# arduino_Uno_mod_bt.net
KiCad netlist of a schematic drawn in EAGLE
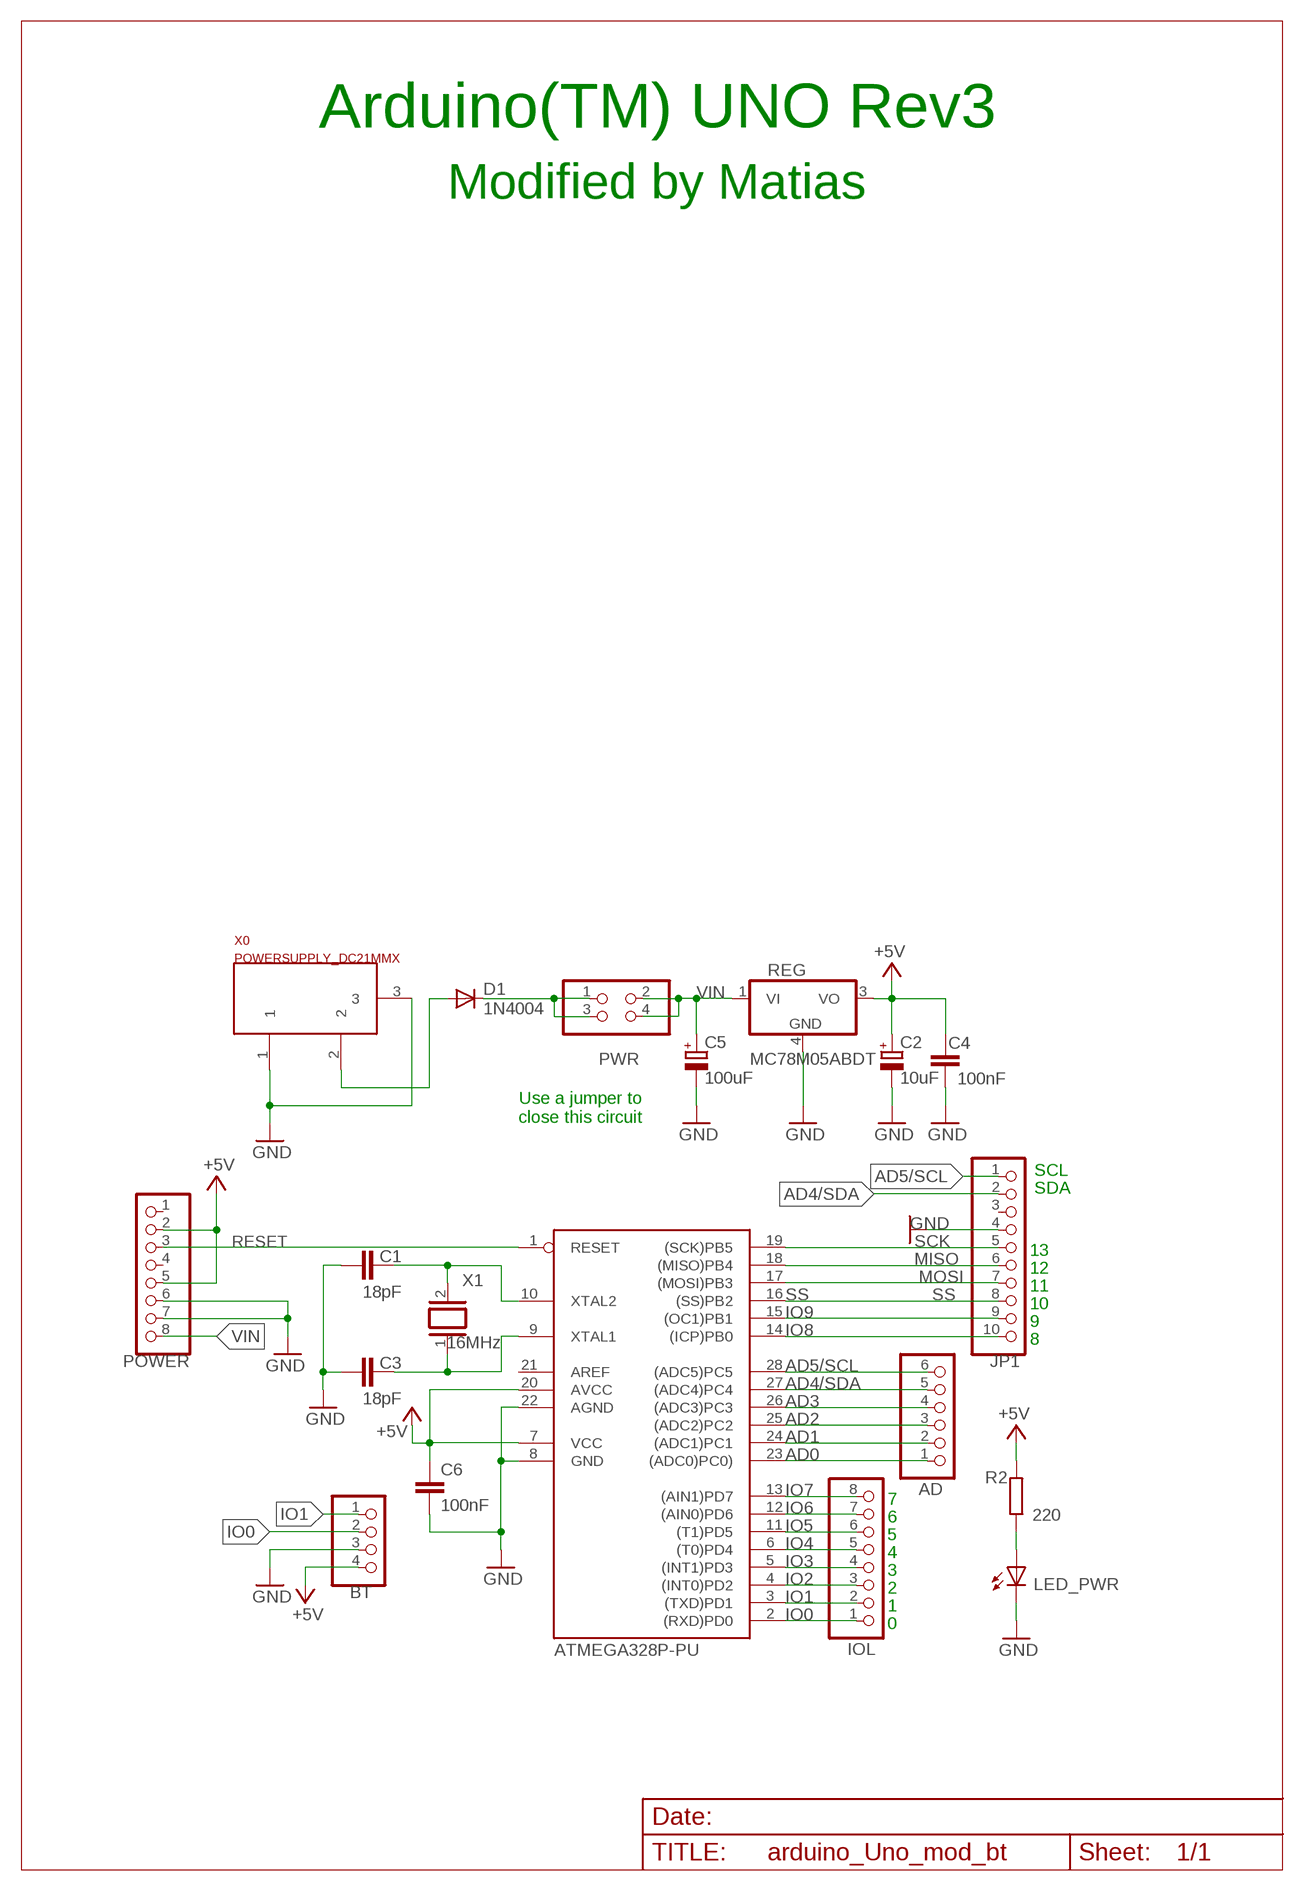
[diagram p0: schematic, sheet 1]

(export (version "E")
  (design (tool "Eeschema 10.0.6"))
  (components
    (comp (ref "AD")
      (value "6x1F-H8.5")
      (footprint "eagle-import:1X06")
      (libsource (lib "eagle-import") (part "PINHD-1X6"))
    )
    (comp (ref "BT")
      (value "PINHD-1X4/90")
      (footprint "eagle-import:1X04_90")
      (libsource (lib "eagle-import") (part "PINHD-1X4/90"))
    )
    (comp (ref "C1")
      (value "18pF")
      (footprint "eagle-import:C025-025X050")
      (libsource (lib "eagle-import") (part "C-EU025-025X050"))
    )
    (comp (ref "C2")
      (value "10uF")
      (footprint "eagle-import:E2,5-5")
      (libsource (lib "eagle-import") (part "CPOL-EUE2.5-5"))
    )
    (comp (ref "C3")
      (value "18pF")
      (footprint "eagle-import:C025-025X050")
      (libsource (lib "eagle-import") (part "C-EU025-025X050"))
    )
    (comp (ref "C4")
      (value "100nF")
      (footprint "eagle-import:C025-025X050")
      (libsource (lib "eagle-import") (part "C-EU025-025X050"))
    )
    (comp (ref "C5")
      (value "100uF")
      (footprint "eagle-import:E2-5")
      (libsource (lib "eagle-import") (part "rcl_334_CPOL-EUE2-5"))
    )
    (comp (ref "C6")
      (value "100nF")
      (footprint "eagle-import:C025-025X050")
      (libsource (lib "eagle-import") (part "C-EU025-025X050"))
    )
    (comp (ref "D1")
      (value "1N4004")
      (footprint "eagle-import:DO41-10")
      (libsource (lib "eagle-import") (part "1N4004"))
    )
    (comp (ref "IOL")
      (value "8x1F-H8.5")
      (footprint "eagle-import:1X08")
      (libsource (lib "eagle-import") (part "PINHD-1X8"))
    )
    (comp (ref "JP1")
      (value "PINHD-1X10")
      (footprint "eagle-import:1X10")
      (libsource (lib "eagle-import") (part "PINHD-1X10"))
    )
    (comp (ref "LED_PWR")
      (value "LED3MM")
      (footprint "eagle-import:LED3MM")
      (libsource (lib "eagle-import") (part "LED3MM"))
    )
    (comp (ref "POWER")
      (value "8x1F-H8.5")
      (footprint "eagle-import:1X08")
      (libsource (lib "eagle-import") (part "PINHD-1X8"))
    )
    (comp (ref "PWR")
      (value "PINHD-2X2")
      (footprint "eagle-import:2X02")
      (libsource (lib "eagle-import") (part "PINHD-2X2"))
    )
    (comp (ref "R2")
      (value "220")
      (footprint "eagle-import:R1206")
      (libsource (lib "eagle-import") (part "R-EU_R1206"))
    )
    (comp (ref "REG")
      (value "MC78M05ABDT")
      (footprint "eagle-import:DPACK_3")
      (libsource (lib "eagle-import") (part "MC78M05ABDT"))
    )
    (comp (ref "X0")
      (value "POWERSUPPLY_DC21MMX")
      (footprint "eagle-import:POWERSUPPLY_DC-21MM")
      (libsource (lib "eagle-import") (part "POWERSUPPLY_DC21MMX"))
    )
    (comp (ref "X1")
      (value "16MHz")
      (footprint "eagle-import:QS")
      (libsource (lib "eagle-import") (part "XTAL/S"))
    )
    (comp (ref "ZU4")
      (value "ATMEGA328P-PU")
      (footprint "eagle-import:DIL28-3")
      (libsource (lib "eagle-import") (part "ATMEGA328P-PU"))
    )
  )
  (nets
    (net (code "1") (name "+5V") (class "Default")
      (node (ref "BT") (pin "4") (pinfunction "4_4") (pintype "passive"))
      (node (ref "C2") (pin "+") (pinfunction "+_+") (pintype "passive"))
      (node (ref "C4") (pin "2") (pinfunction "2_2") (pintype "passive"))
      (node (ref "C6") (pin "1") (pinfunction "1_1") (pintype "passive"))
      (node (ref "POWER") (pin "2") (pinfunction "2_2") (pintype "passive"))
      (node (ref "POWER") (pin "5") (pinfunction "5_5") (pintype "passive"))
      (node (ref "R2") (pin "2") (pinfunction "2_2") (pintype "passive"))
      (node (ref "REG") (pin "3") (pinfunction "VO_3") (pintype "passive"))
      (node (ref "ZU4") (pin "20") (pinfunction "AVCC_20") (pintype "power_in"))
      (node (ref "ZU4") (pin "7") (pinfunction "VCC_7") (pintype "power_in"))
    )
    (net (code "2") (name "/AD0") (class "Default")
      (node (ref "AD") (pin "1") (pinfunction "1_1") (pintype "passive"))
      (node (ref "ZU4") (pin "23") (pinfunction "(ADC0)PC0)_23") (pintype "bidirectional"))
    )
    (net (code "3") (name "/AD1") (class "Default")
      (node (ref "AD") (pin "2") (pinfunction "2_2") (pintype "passive"))
      (node (ref "ZU4") (pin "24") (pinfunction "(ADC1)PC1_24") (pintype "bidirectional"))
    )
    (net (code "4") (name "/AD2") (class "Default")
      (node (ref "AD") (pin "3") (pinfunction "3_3") (pintype "passive"))
      (node (ref "ZU4") (pin "25") (pinfunction "(ADC2)PC2_25") (pintype "bidirectional"))
    )
    (net (code "5") (name "/AD3") (class "Default")
      (node (ref "AD") (pin "4") (pinfunction "4_4") (pintype "passive"))
      (node (ref "ZU4") (pin "26") (pinfunction "(ADC3)PC3_26") (pintype "bidirectional"))
    )
    (net (code "6") (name "/IO2") (class "Default")
      (node (ref "IOL") (pin "3") (pinfunction "3_3") (pintype "passive"))
      (node (ref "ZU4") (pin "4") (pinfunction "(INT0)PD2_4") (pintype "bidirectional"))
    )
    (net (code "7") (name "/IO3") (class "Default")
      (node (ref "IOL") (pin "4") (pinfunction "4_4") (pintype "passive"))
      (node (ref "ZU4") (pin "5") (pinfunction "(INT1)PD3_5") (pintype "bidirectional"))
    )
    (net (code "8") (name "/IO4") (class "Default")
      (node (ref "IOL") (pin "5") (pinfunction "5_5") (pintype "passive"))
      (node (ref "ZU4") (pin "6") (pinfunction "(T0)PD4_6") (pintype "bidirectional"))
    )
    (net (code "9") (name "/IO5") (class "Default")
      (node (ref "IOL") (pin "6") (pinfunction "6_6") (pintype "passive"))
      (node (ref "ZU4") (pin "11") (pinfunction "(T1)PD5_11") (pintype "bidirectional"))
    )
    (net (code "10") (name "/IO6") (class "Default")
      (node (ref "IOL") (pin "7") (pinfunction "7_7") (pintype "passive"))
      (node (ref "ZU4") (pin "12") (pinfunction "(AIN0)PD6_12") (pintype "bidirectional"))
    )
    (net (code "11") (name "/IO7") (class "Default")
      (node (ref "IOL") (pin "8") (pinfunction "8_8") (pintype "passive"))
      (node (ref "ZU4") (pin "13") (pinfunction "(AIN1)PD7_13") (pintype "bidirectional"))
    )
    (net (code "12") (name "/IO8") (class "Default")
      (node (ref "JP1") (pin "10") (pinfunction "10_10") (pintype "passive"))
      (node (ref "ZU4") (pin "14") (pinfunction "(ICP)PB0_14") (pintype "bidirectional"))
    )
    (net (code "13") (name "/IO9") (class "Default")
      (node (ref "JP1") (pin "9") (pinfunction "9_9") (pintype "passive"))
      (node (ref "ZU4") (pin "15") (pinfunction "(OC1)PB1_15") (pintype "bidirectional"))
    )
    (net (code "14") (name "/MISO") (class "Default")
      (node (ref "JP1") (pin "6") (pinfunction "6_6") (pintype "passive"))
      (node (ref "ZU4") (pin "18") (pinfunction "(MISO)PB4_18") (pintype "bidirectional"))
    )
    (net (code "15") (name "/MOSI") (class "Default")
      (node (ref "JP1") (pin "7") (pinfunction "7_7") (pintype "passive"))
      (node (ref "ZU4") (pin "17") (pinfunction "(MOSI)PB3_17") (pintype "bidirectional"))
    )
    (net (code "16") (name "/RESET") (class "Default")
      (node (ref "POWER") (pin "3") (pinfunction "3_3") (pintype "passive"))
      (node (ref "ZU4") (pin "1") (pinfunction "RESET_1") (pintype "input"))
    )
    (net (code "17") (name "/SCK") (class "Default")
      (node (ref "JP1") (pin "5") (pinfunction "5_5") (pintype "passive"))
      (node (ref "ZU4") (pin "19") (pinfunction "(SCK)PB5_19") (pintype "bidirectional"))
    )
    (net (code "18") (name "/SS") (class "Default")
      (node (ref "JP1") (pin "8") (pinfunction "8_8") (pintype "passive"))
      (node (ref "ZU4") (pin "16") (pinfunction "(SS)PB2_16") (pintype "bidirectional"))
    )
    (net (code "19") (name "AD4{slash}SDA") (class "Default")
      (node (ref "AD") (pin "5") (pinfunction "5_5") (pintype "passive"))
      (node (ref "JP1") (pin "2") (pinfunction "2_2") (pintype "passive"))
      (node (ref "ZU4") (pin "27") (pinfunction "(ADC4)PC4_27") (pintype "bidirectional"))
    )
    (net (code "20") (name "AD5{slash}SCL") (class "Default")
      (node (ref "AD") (pin "6") (pinfunction "6_6") (pintype "passive"))
      (node (ref "JP1") (pin "1") (pinfunction "1_1") (pintype "passive"))
      (node (ref "ZU4") (pin "28") (pinfunction "(ADC5)PC5_28") (pintype "bidirectional"))
    )
    (net (code "21") (name "GND") (class "Default")
      (node (ref "BT") (pin "3") (pinfunction "3_3") (pintype "passive"))
      (node (ref "C1") (pin "1") (pinfunction "1_1") (pintype "passive"))
      (node (ref "C2") (pin "-") (pinfunction "-_-") (pintype "passive"))
      (node (ref "C3") (pin "1") (pinfunction "1_1") (pintype "passive"))
      (node (ref "C4") (pin "1") (pinfunction "1_1") (pintype "passive"))
      (node (ref "C5") (pin "-") (pinfunction "-_-") (pintype "passive"))
      (node (ref "C6") (pin "2") (pinfunction "2_2") (pintype "passive"))
      (node (ref "JP1") (pin "4") (pinfunction "4_4") (pintype "passive"))
      (node (ref "LED_PWR") (pin "K") (pinfunction "C_K") (pintype "passive"))
      (node (ref "POWER") (pin "6") (pinfunction "6_6") (pintype "passive"))
      (node (ref "POWER") (pin "7") (pinfunction "7_7") (pintype "passive"))
      (node (ref "REG") (pin "4") (pinfunction "GND_4") (pintype "passive"))
      (node (ref "X0") (pin "1") (pinfunction "1_1") (pintype "power_in"))
      (node (ref "X0") (pin "3") (pinfunction "3_3") (pintype "power_in"))
      (node (ref "ZU4") (pin "22") (pinfunction "AGND_22") (pintype "power_in"))
      (node (ref "ZU4") (pin "8") (pinfunction "GND_8") (pintype "power_in"))
    )
    (net (code "22") (name "IO0") (class "Default")
      (node (ref "BT") (pin "2") (pinfunction "2_2") (pintype "passive"))
      (node (ref "IOL") (pin "1") (pinfunction "1_1") (pintype "passive"))
      (node (ref "ZU4") (pin "2") (pinfunction "(RXD)PD0_2") (pintype "bidirectional"))
    )
    (net (code "23") (name "IO1") (class "Default")
      (node (ref "BT") (pin "1") (pinfunction "1_1") (pintype "passive"))
      (node (ref "IOL") (pin "2") (pinfunction "2_2") (pintype "passive"))
      (node (ref "ZU4") (pin "3") (pinfunction "(TXD)PD1_3") (pintype "bidirectional"))
    )
    (net (code "24") (name "Net-(D1-PadA)") (class "Default")
      (node (ref "D1") (pin "A") (pinfunction "A_A") (pintype "passive"))
      (node (ref "X0") (pin "2") (pinfunction "2_2") (pintype "power_in"))
    )
    (net (code "25") (name "Net-(D1-PadC)") (class "Default")
      (node (ref "D1") (pin "C") (pinfunction "C_C") (pintype "passive"))
      (node (ref "PWR") (pin "1") (pinfunction "1_1") (pintype "passive"))
      (node (ref "PWR") (pin "3") (pinfunction "3_3") (pintype "passive"))
    )
    (net (code "26") (name "Net-(LED_PWR-PadA)") (class "Default")
      (node (ref "LED_PWR") (pin "A") (pinfunction "A_A") (pintype "passive"))
      (node (ref "R2") (pin "1") (pinfunction "1_1") (pintype "passive"))
    )
    (net (code "27") (name "Net-(ZU4-XTAL1)") (class "Default")
      (node (ref "C3") (pin "2") (pinfunction "2_2") (pintype "passive"))
      (node (ref "X1") (pin "1") (pinfunction "1_1") (pintype "passive"))
      (node (ref "ZU4") (pin "9") (pinfunction "XTAL1_9") (pintype "bidirectional"))
    )
    (net (code "28") (name "Net-(ZU4-XTAL2)") (class "Default")
      (node (ref "C1") (pin "2") (pinfunction "2_2") (pintype "passive"))
      (node (ref "X1") (pin "2") (pinfunction "2_2") (pintype "passive"))
      (node (ref "ZU4") (pin "10") (pinfunction "XTAL2_10") (pintype "bidirectional"))
    )
    (net (code "29") (name "VIN") (class "Default")
      (node (ref "C5") (pin "+") (pinfunction "+_+") (pintype "passive"))
      (node (ref "POWER") (pin "8") (pinfunction "8_8") (pintype "passive"))
      (node (ref "PWR") (pin "2") (pinfunction "2_2") (pintype "passive"))
      (node (ref "PWR") (pin "4") (pinfunction "4_4") (pintype "passive"))
      (node (ref "REG") (pin "1") (pinfunction "VI_1") (pintype "input"))
    )
    (net (code "30") (name "unconnected-(JP1-Pad3)") (class "Default")
      (node (ref "JP1") (pin "3") (pinfunction "3_3") (pintype "passive"))
    )
    (net (code "31") (name "unconnected-(POWER-Pad1)") (class "Default")
      (node (ref "POWER") (pin "1") (pinfunction "1_1") (pintype "passive"))
    )
    (net (code "32") (name "unconnected-(POWER-Pad4)") (class "Default")
      (node (ref "POWER") (pin "4") (pinfunction "4_4") (pintype "passive"))
    )
    (net (code "33") (name "unconnected-(ZU4-AREF-Pad21)") (class "Default")
      (node (ref "ZU4") (pin "21") (pinfunction "AREF_21") (pintype "passive"))
    )
  )
)
